# mm_robot_pcb_v6.net
KiCad netlist of a schematic drawn in EAGLE
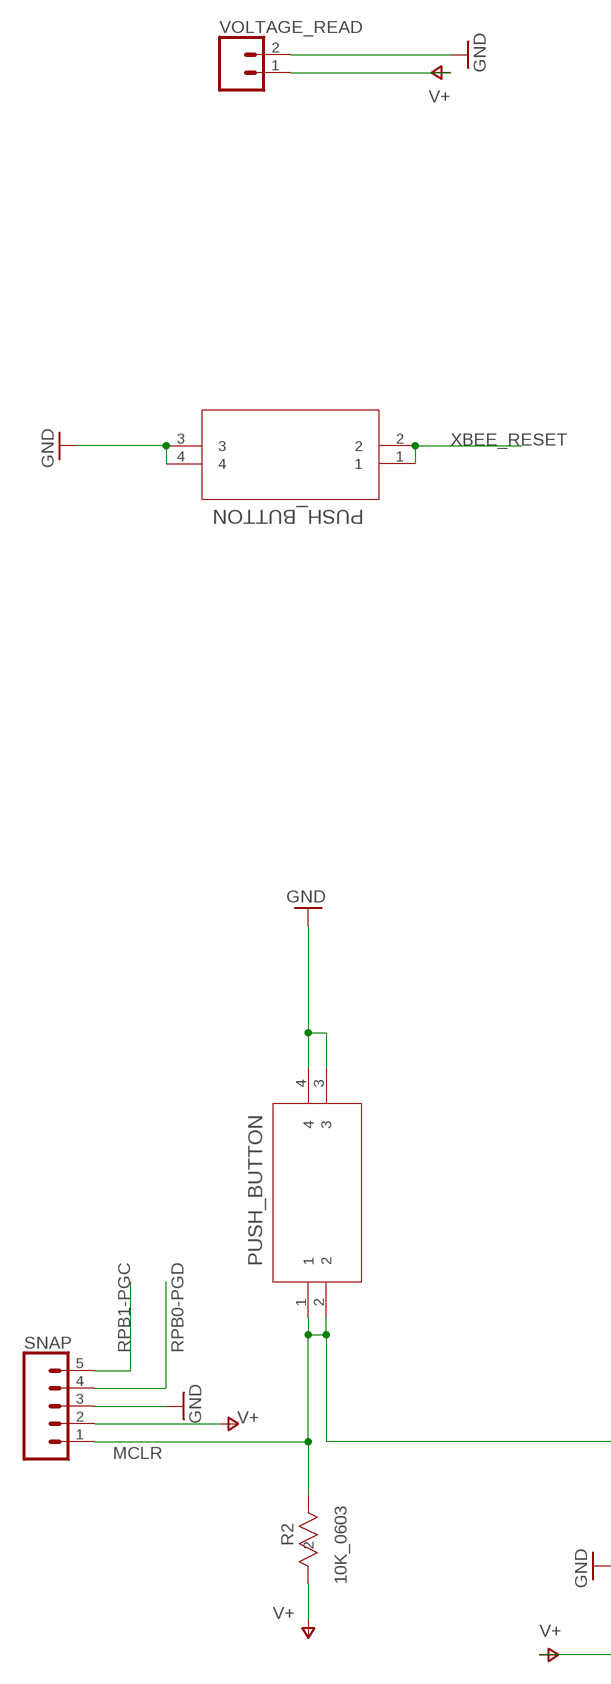
[diagram p0: schematic, sheet 1, part 1 of 2]
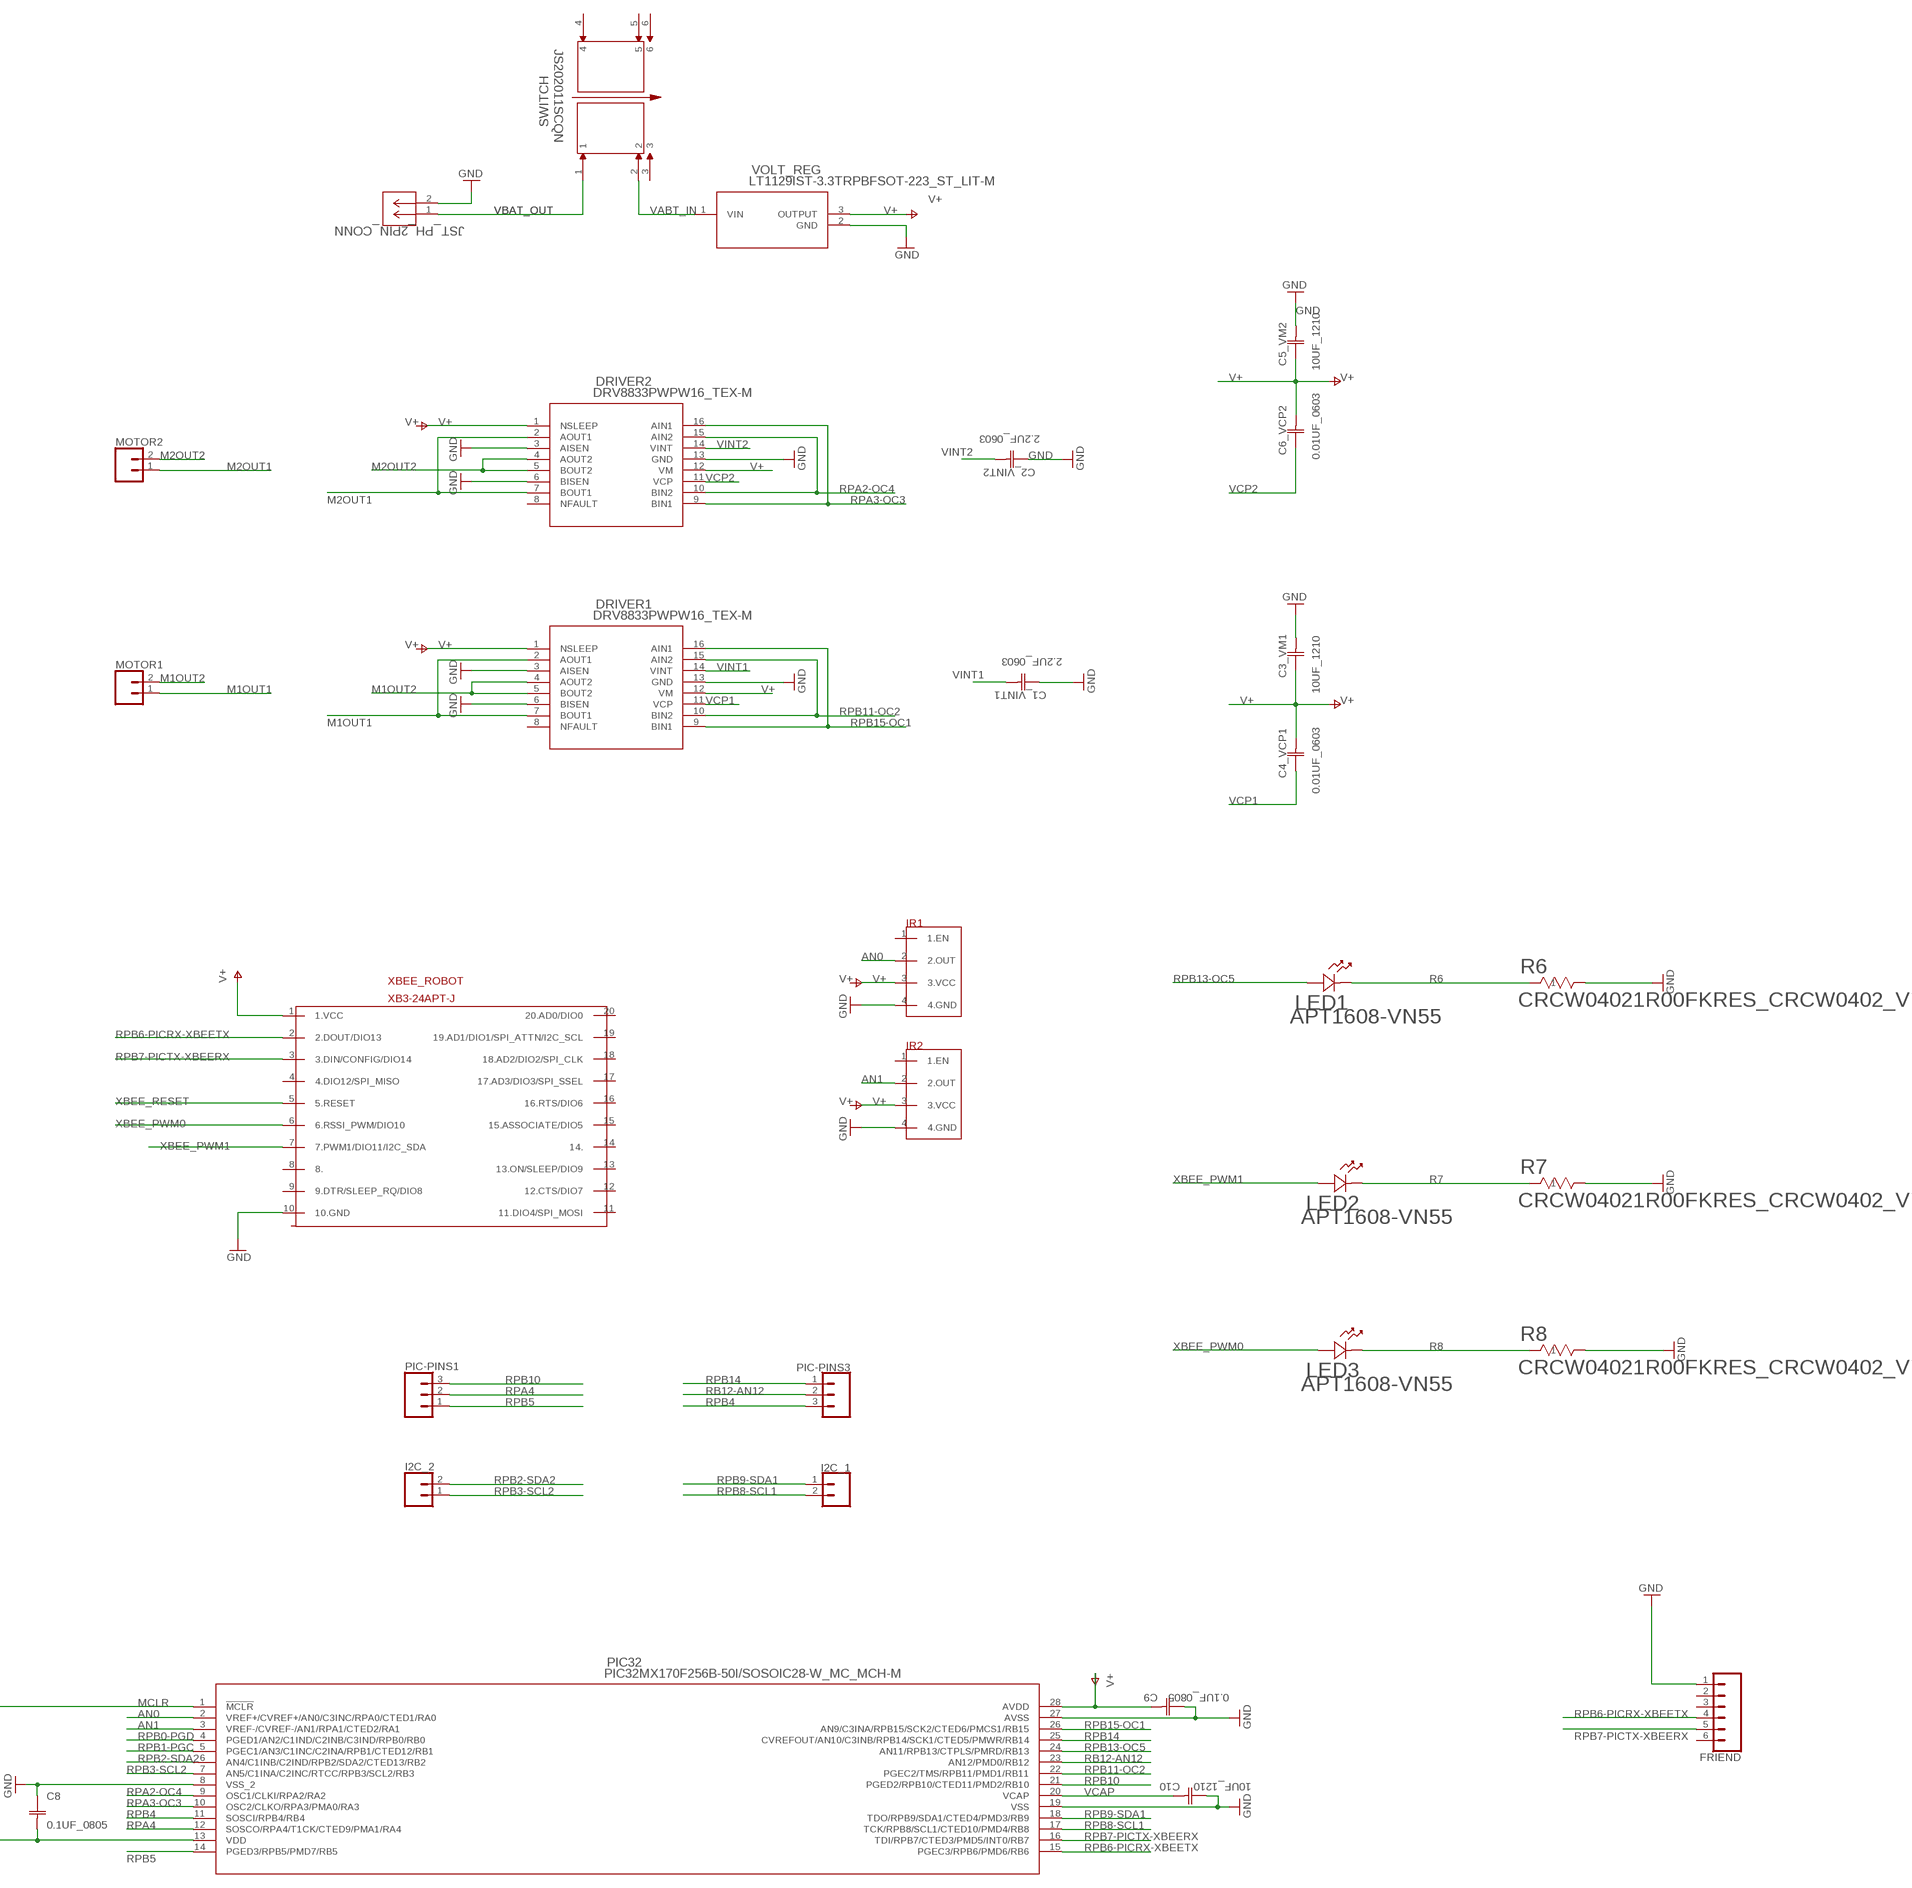
[diagram p1: schematic, sheet 1, part 2 of 2]

(export (version "E")
  (design (tool "Eeschema 10.0.6"))
  (components
    (comp (ref "C1_VINT1")
      (value "2.2UF_0603")
      (footprint "eagle-import:CAP_CL10_SAM-M")
      (fields
        (field (name "MANUFACTURER_PART_NUMBER") "CL10A225KP8NNNC")
        (field (name "COPYRIGHT") "Copyright (C) 2021 Ultra Librarian. All rights reserved.")
      )
      (libsource (lib "eagle-import") (part "CL10A225KP8NNNCCAP_CL10_SAM-M"))
    )
    (comp (ref "C2_VINT2")
      (value "2.2UF_0603")
      (footprint "eagle-import:CAP_CL10_SAM-M")
      (fields
        (field (name "MANUFACTURER_PART_NUMBER") "CL10A225KP8NNNC")
        (field (name "COPYRIGHT") "Copyright (C) 2021 Ultra Librarian. All rights reserved.")
      )
      (libsource (lib "eagle-import") (part "CL10A225KP8NNNCCAP_CL10_SAM-M"))
    )
    (comp (ref "C3_VM1")
      (value "10UF_1210")
      (footprint "eagle-import:CAP_TPS_B_AVX-M")
      (fields
        (field (name "MANUFACTURER_PART_NUMBER") "TPSB106K016R0500")
        (field (name "COPYRIGHT") "Copyright (C) 2021 Ultra Librarian. All rights reserved.")
      )
      (libsource (lib "eagle-import") (part "TPSB106K016R0500CAP_TPS_B_AVX-M"))
    )
    (comp (ref "C4_VCP1")
      (value "0.01UF_0603")
      (footprint "eagle-import:CAP_01UF_0603_X7R_G_AVX")
      (libsource (lib "eagle-import") (part "01UF_CAP"))
    )
    (comp (ref "C5_VM2")
      (value "10UF_1210")
      (footprint "eagle-import:CAP_TPS_B_AVX-M")
      (fields
        (field (name "MANUFACTURER_PART_NUMBER") "TPSB106K016R0500")
        (field (name "COPYRIGHT") "Copyright (C) 2021 Ultra Librarian. All rights reserved.")
      )
      (libsource (lib "eagle-import") (part "TPSB106K016R0500CAP_TPS_B_AVX-M"))
    )
    (comp (ref "C6_VCP2")
      (value "0.01UF_0603")
      (footprint "eagle-import:CAP_01UF_0603_X7R_G_AVX")
      (libsource (lib "eagle-import") (part "01UF_CAP"))
    )
    (comp (ref "C8")
      (value "0.1UF_0805")
      (footprint "eagle-import:CAP_C2012X7R2A104K125AA_TDK-M")
      (fields
        (field (name "MANUFACTURER_PART_NUMBER") "C2012X7R2A104K125AA")
        (field (name "COPYRIGHT") "Copyright (C) 2021 Ultra Librarian. All rights reserved.")
      )
      (libsource (lib "eagle-import") (part "C2012X7R2A104K125AACAP_C2012X7R2A104K125AA_TDK-M"))
    )
    (comp (ref "C9")
      (value "0.1UF_0805")
      (footprint "eagle-import:CAP_C2012X7R2A104K125AA_TDK-M")
      (fields
        (field (name "MANUFACTURER_PART_NUMBER") "C2012X7R2A104K125AA")
        (field (name "COPYRIGHT") "Copyright (C) 2021 Ultra Librarian. All rights reserved.")
      )
      (libsource (lib "eagle-import") (part "C2012X7R2A104K125AACAP_C2012X7R2A104K125AA_TDK-M"))
    )
    (comp (ref "C10")
      (value "10UF_1210")
      (footprint "eagle-import:CAP_TPS_B_AVX-M")
      (fields
        (field (name "MANUFACTURER_PART_NUMBER") "TPSB106K016R0500")
        (field (name "COPYRIGHT") "Copyright (C) 2021 Ultra Librarian. All rights reserved.")
      )
      (libsource (lib "eagle-import") (part "TPSB106K016R0500CAP_TPS_B_AVX-M"))
    )
    (comp (ref "DRIVER1")
      (value "DRV8833PWPW16_TEX-M")
      (footprint "eagle-import:PW16_TEX-M")
      (fields
        (field (name "MANUFACTURER_PART_NUMBER") "DRV8833PW")
        (field (name "COPYRIGHT") "Copyright (C) 2021 Ultra Librarian. All rights reserved.")
      )
      (libsource (lib "eagle-import") (part "DRV8833PWPW16_TEX-M"))
    )
    (comp (ref "DRIVER2")
      (value "DRV8833PWPW16_TEX-M")
      (footprint "eagle-import:PW16_TEX-M")
      (fields
        (field (name "MANUFACTURER_PART_NUMBER") "DRV8833PW")
        (field (name "COPYRIGHT") "Copyright (C) 2021 Ultra Librarian. All rights reserved.")
      )
      (libsource (lib "eagle-import") (part "DRV8833PWPW16_TEX-M"))
    )
    (comp (ref "FRIEND")
      (value "CONN_06NO_SILK_FEMALE_PTH")
      (footprint "eagle-import:1X06_NO_SILK")
      (libsource (lib "eagle-import") (part "CONN_06NO_SILK_FEMALE_PTH"))
    )
    (comp (ref "I2C_1")
      (value "CONN_02")
      (footprint "eagle-import:1X02")
      (libsource (lib "eagle-import") (part "CONN_02"))
    )
    (comp (ref "I2C_2")
      (value "CONN_02")
      (footprint "eagle-import:1X02")
      (libsource (lib "eagle-import") (part "CONN_02"))
    )
    (comp (ref "IR1")
      (value "GP2Y0A60SZLF")
      (footprint "eagle-import:1X04")
      (libsource (lib "eagle-import") (part "GP2Y0A60SZLF"))
    )
    (comp (ref "IR2")
      (value "GP2Y0A60SZLF")
      (footprint "eagle-import:1X04")
      (libsource (lib "eagle-import") (part "GP2Y0A60SZLF"))
    )
    (comp (ref "JST_PH_2PIN_CONN")
      (value "1769")
      (footprint "eagle-import:CONN_1769_ADA")
      (fields (field (name "COPYRIGHT") "Copyright (C) 2021 Ultra Librarian. All rights reserved."))
      (libsource (lib "eagle-import") (part "1769"))
    )
    (comp (ref "LED1")
      (value "APT1608-VN55")
      (footprint "eagle-import:LED_APT1608_KNB")
      (fields (field (name "COPYRIGHT") "Copyright (C) 2021 Ultra Librarian. All rights reserved."))
      (libsource (lib "eagle-import") (part "APT1608-VN55"))
    )
    (comp (ref "LED2")
      (value "APT1608-VN55")
      (footprint "eagle-import:LED_APT1608_KNB")
      (fields (field (name "COPYRIGHT") "Copyright (C) 2021 Ultra Librarian. All rights reserved."))
      (libsource (lib "eagle-import") (part "APT1608-VN55"))
    )
    (comp (ref "LED3")
      (value "APT1608-VN55")
      (footprint "eagle-import:LED_APT1608_KNB")
      (fields (field (name "COPYRIGHT") "Copyright (C) 2021 Ultra Librarian. All rights reserved."))
      (libsource (lib "eagle-import") (part "APT1608-VN55"))
    )
    (comp (ref "MOTOR1")
      (value "CONN_02")
      (footprint "eagle-import:1X02")
      (libsource (lib "eagle-import") (part "CONN_02"))
    )
    (comp (ref "MOTOR2")
      (value "CONN_02")
      (footprint "eagle-import:1X02")
      (libsource (lib "eagle-import") (part "CONN_02"))
    )
    (comp (ref "PIC-PINS1")
      (value "455-1750-1-ND")
      (footprint "eagle-import:1X03")
      (libsource (lib "eagle-import") (part "CONN_03"))
    )
    (comp (ref "PIC-PINS3")
      (value "455-1750-1-ND")
      (footprint "eagle-import:1X03")
      (libsource (lib "eagle-import") (part "CONN_03"))
    )
    (comp (ref "PIC32")
      (value "PIC32MX170F256B-50I/SOSOIC28-W_MC_MCH-M")
      (footprint "eagle-import:SOIC28-W_MC_MCH-M")
      (fields
        (field (name "MANUFACTURER_PART_NUMBER") "PIC32MX170F256B-50I/SO")
        (field (name "COPYRIGHT") "Copyright (C) 2021 Ultra Librarian. All rights reserved.")
      )
      (libsource (lib "eagle-import") (part "PIC32MX170F256B-50I/SOSOIC28-W_MC_MCH-M"))
    )
    (comp (ref "PIC_PB")
      (value "PUSH_BUTTON")
      (footprint "eagle-import:SMT_FS-M")
      (fields
        (field (name "MANUFACTURER_PART_NUMBER") "PTS526 SK15 SMTR2 LFS")
        (field (name "COPYRIGHT") "Copyright (C) 2021 Ultra Librarian. All rights reserved.")
      )
      (libsource (lib "eagle-import") (part "PTS526_SK15_SMTR2_LFSSMT_FS-M"))
    )
    (comp (ref "R2")
      (value "10K_0603")
      (footprint "eagle-import:RES0603_CRG_TYCO_TYC-M")
      (fields
        (field (name "MANUFACTURER_PART_NUMBER") "CRG0603F10K")
        (field (name "COPYRIGHT") "Copyright (C) 2021 Ultra Librarian. All rights reserved.")
      )
      (libsource (lib "eagle-import") (part "CRG0603F10KRES0603_CRG_TYCO_TYC-M"))
    )
    (comp (ref "R6")
      (value "CRCW04021R00FKRES_CRCW0402_VIS-M")
      (footprint "eagle-import:RES_CRCW0402_VIS-M")
      (fields
        (field (name "MANUFACTURER_PART_NUMBER") "CRCW04021R00FK")
        (field (name "COPYRIGHT") "Copyright (C) 2021 Ultra Librarian. All rights reserved.")
      )
      (libsource (lib "eagle-import") (part "CRCW04021R00FKRES_CRCW0402_VIS-M"))
    )
    (comp (ref "R7")
      (value "CRCW04021R00FKRES_CRCW0402_VIS-M")
      (footprint "eagle-import:RES_CRCW0402_VIS-M")
      (fields
        (field (name "MANUFACTURER_PART_NUMBER") "CRCW04021R00FK")
        (field (name "COPYRIGHT") "Copyright (C) 2021 Ultra Librarian. All rights reserved.")
      )
      (libsource (lib "eagle-import") (part "CRCW04021R00FKRES_CRCW0402_VIS-M"))
    )
    (comp (ref "R8")
      (value "CRCW04021R00FKRES_CRCW0402_VIS-M")
      (footprint "eagle-import:RES_CRCW0402_VIS-M")
      (fields
        (field (name "MANUFACTURER_PART_NUMBER") "CRCW04021R00FK")
        (field (name "COPYRIGHT") "Copyright (C) 2021 Ultra Librarian. All rights reserved.")
      )
      (libsource (lib "eagle-import") (part "CRCW04021R00FKRES_CRCW0402_VIS-M"))
    )
    (comp (ref "SNAP")
      (value "CONN_05")
      (footprint "eagle-import:1X05")
      (libsource (lib "eagle-import") (part "CONN_05"))
    )
    (comp (ref "SWITCH")
      (value "JS202011SCQN")
      (footprint "eagle-import:SW_JS202011SCQN")
      (fields (field (name "COPYRIGHT") "Copyright (C) 2021 Ultra Librarian. All rights reserved."))
      (libsource (lib "eagle-import") (part "JS202011SCQN"))
    )
    (comp (ref "VOLTAGE_READ")
      (value "CONN_02")
      (footprint "eagle-import:1X02")
      (libsource (lib "eagle-import") (part "CONN_02"))
    )
    (comp (ref "VOLT_REG")
      (value "LT1129IST-3.3TRPBFSOT-223_ST_LIT-M")
      (footprint "eagle-import:SOT-223_ST_LIT-M")
      (fields
        (field (name "MANUFACTURER_PART_NUMBER") "LT1129IST-3.3#TRPBF")
        (field (name "COPYRIGHT") "Copyright (C) 2021 Ultra Librarian. All rights reserved.")
      )
      (libsource (lib "eagle-import") (part "LT1129IST-3.3TRPBFSOT-223_ST_LIT-M"))
    )
    (comp (ref "XBEE_PB")
      (value "PUSH_BUTTON")
      (footprint "eagle-import:SMT_FS-M")
      (fields
        (field (name "MANUFACTURER_PART_NUMBER") "PTS526 SK15 SMTR2 LFS")
        (field (name "COPYRIGHT") "Copyright (C) 2021 Ultra Librarian. All rights reserved.")
      )
      (libsource (lib "eagle-import") (part "PTS526_SK15_SMTR2_LFSSMT_FS-M"))
    )
    (comp (ref "XBEE_ROBOT")
      (value "XB3-24APT-J")
      (footprint "eagle-import:XB3-24APT-J")
      (libsource (lib "eagle-import") (part "XB3-24APT-J"))
    )
  )
  (nets
    (net (code "1") (name "/AN0") (class "Default")
      (node (ref "IR1") (pin "2") (pinfunction "2.OUT_2") (pintype "bidirectional"))
      (node (ref "PIC32") (pin "2") (pinfunction "VREF+/CVREF+/AN0/C3INC/RPA0/CTED1/RA0_2") (pintype "bidirectional"))
    )
    (net (code "2") (name "/AN1") (class "Default")
      (node (ref "IR2") (pin "2") (pinfunction "2.OUT_2") (pintype "bidirectional"))
      (node (ref "PIC32") (pin "3") (pinfunction "VREF-/CVREF-/AN1/RPA1/CTED2/RA1_3") (pintype "bidirectional"))
    )
    (net (code "3") (name "/M1OUT1") (class "Default")
      (node (ref "DRIVER1") (pin "2") (pinfunction "AOUT1_2") (pintype "output"))
      (node (ref "DRIVER1") (pin "7") (pinfunction "BOUT1_7") (pintype "output"))
      (node (ref "MOTOR1") (pin "1") (pinfunction "1_1") (pintype "passive"))
    )
    (net (code "4") (name "/M1OUT2") (class "Default")
      (node (ref "DRIVER1") (pin "4") (pinfunction "AOUT2_4") (pintype "output"))
      (node (ref "DRIVER1") (pin "5") (pinfunction "BOUT2_5") (pintype "output"))
      (node (ref "MOTOR1") (pin "2") (pinfunction "2_2") (pintype "passive"))
    )
    (net (code "5") (name "/M2OUT1") (class "Default")
      (node (ref "DRIVER2") (pin "2") (pinfunction "AOUT1_2") (pintype "output"))
      (node (ref "DRIVER2") (pin "7") (pinfunction "BOUT1_7") (pintype "output"))
      (node (ref "MOTOR2") (pin "1") (pinfunction "1_1") (pintype "passive"))
    )
    (net (code "6") (name "/M2OUT2") (class "Default")
      (node (ref "DRIVER2") (pin "4") (pinfunction "AOUT2_4") (pintype "output"))
      (node (ref "DRIVER2") (pin "5") (pinfunction "BOUT2_5") (pintype "output"))
      (node (ref "MOTOR2") (pin "2") (pinfunction "2_2") (pintype "passive"))
    )
    (net (code "7") (name "/MCLR") (class "Default")
      (node (ref "PIC32") (pin "1") (pinfunction "~{MCLR}_1") (pintype "bidirectional"))
      (node (ref "PIC_PB") (pin "1") (pinfunction "1_1") (pintype "passive"))
      (node (ref "PIC_PB") (pin "2") (pinfunction "2_2") (pintype "passive"))
      (node (ref "R2") (pin "1") (pinfunction "1_1") (pintype "passive"))
      (node (ref "SNAP") (pin "1") (pinfunction "1_1") (pintype "passive"))
    )
    (net (code "8") (name "/R6") (class "Default")
      (node (ref "LED1") (pin "1") (pinfunction "1_1") (pintype "passive"))
      (node (ref "R6") (pin "1") (pinfunction "1_1") (pintype "passive"))
    )
    (net (code "9") (name "/R7") (class "Default")
      (node (ref "LED2") (pin "1") (pinfunction "1_1") (pintype "passive"))
      (node (ref "R7") (pin "1") (pinfunction "1_1") (pintype "passive"))
    )
    (net (code "10") (name "/R8") (class "Default")
      (node (ref "LED3") (pin "1") (pinfunction "1_1") (pintype "passive"))
      (node (ref "R8") (pin "1") (pinfunction "1_1") (pintype "passive"))
    )
    (net (code "11") (name "/RB12-AN12") (class "Default")
      (node (ref "PIC-PINS3") (pin "2") (pinfunction "2_2") (pintype "passive"))
      (node (ref "PIC32") (pin "23") (pinfunction "AN12/PMD0/RB12_23") (pintype "bidirectional"))
    )
    (net (code "12") (name "/RPA2-OC4") (class "Default")
      (node (ref "DRIVER2") (pin "10") (pinfunction "BIN2_10") (pintype "input"))
      (node (ref "DRIVER2") (pin "15") (pinfunction "AIN2_15") (pintype "input"))
      (node (ref "PIC32") (pin "9") (pinfunction "OSC1/CLKI/RPA2/RA2_9") (pintype "bidirectional"))
    )
    (net (code "13") (name "/RPA3-OC3") (class "Default")
      (node (ref "DRIVER2") (pin "16") (pinfunction "AIN1_16") (pintype "input"))
      (node (ref "DRIVER2") (pin "9") (pinfunction "BIN1_9") (pintype "input"))
      (node (ref "PIC32") (pin "10") (pinfunction "OSC2/CLKO/RPA3/PMA0/RA3_10") (pintype "bidirectional"))
    )
    (net (code "14") (name "/RPA4") (class "Default")
      (node (ref "PIC-PINS1") (pin "2") (pinfunction "2_2") (pintype "passive"))
      (node (ref "PIC32") (pin "12") (pinfunction "SOSCO/RPA4/T1CK/CTED9/PMA1/RA4_12") (pintype "bidirectional"))
    )
    (net (code "15") (name "/RPB0-PGD") (class "Default")
      (node (ref "PIC32") (pin "4") (pinfunction "PGED1/AN2/C1IND/C2INB/C3IND/RPB0/RB0_4") (pintype "bidirectional"))
      (node (ref "SNAP") (pin "4") (pinfunction "4_4") (pintype "passive"))
    )
    (net (code "16") (name "/RPB1-PGC") (class "Default")
      (node (ref "PIC32") (pin "5") (pinfunction "PGEC1/AN3/C1INC/C2INA/RPB1/CTED12/RB1_5") (pintype "bidirectional"))
      (node (ref "SNAP") (pin "5") (pinfunction "5_5") (pintype "passive"))
    )
    (net (code "17") (name "/RPB2-SDA2") (class "Default")
      (node (ref "I2C_2") (pin "2") (pinfunction "2_2") (pintype "passive"))
      (node (ref "PIC32") (pin "6") (pinfunction "AN4/C1INB/C2IND/RPB2/SDA2/CTED13/RB2_6") (pintype "bidirectional"))
    )
    (net (code "18") (name "/RPB3-SCL2") (class "Default")
      (node (ref "I2C_2") (pin "1") (pinfunction "1_1") (pintype "passive"))
      (node (ref "PIC32") (pin "7") (pinfunction "AN5/C1INA/C2INC/RTCC/RPB3/SCL2/RB3_7") (pintype "bidirectional"))
    )
    (net (code "19") (name "/RPB4") (class "Default")
      (node (ref "PIC-PINS3") (pin "3") (pinfunction "3_3") (pintype "passive"))
      (node (ref "PIC32") (pin "11") (pinfunction "SOSCI/RPB4/RB4_11") (pintype "bidirectional"))
    )
    (net (code "20") (name "/RPB5") (class "Default")
      (node (ref "PIC-PINS1") (pin "1") (pinfunction "1_1") (pintype "passive"))
      (node (ref "PIC32") (pin "14") (pinfunction "PGED3/RPB5/PMD7/RB5_14") (pintype "bidirectional"))
    )
    (net (code "21") (name "/RPB6-PICRX-XBEETX") (class "Default")
      (node (ref "FRIEND") (pin "4") (pinfunction "4_4") (pintype "passive"))
      (node (ref "PIC32") (pin "15") (pinfunction "PGEC3/RPB6/PMD6/RB6_15") (pintype "bidirectional"))
      (node (ref "XBEE_ROBOT") (pin "2") (pinfunction "2.DOUT/DIO13_2") (pintype "bidirectional"))
    )
    (net (code "22") (name "/RPB7-PICTX-XBEERX") (class "Default")
      (node (ref "FRIEND") (pin "5") (pinfunction "5_5") (pintype "passive"))
      (node (ref "PIC32") (pin "16") (pinfunction "TDI/RPB7/CTED3/PMD5/INT0/RB7_16") (pintype "bidirectional"))
      (node (ref "XBEE_ROBOT") (pin "3") (pinfunction "3.DIN/CONFIG/DIO14_3") (pintype "bidirectional"))
    )
    (net (code "23") (name "/RPB8-SCL1") (class "Default")
      (node (ref "I2C_1") (pin "2") (pinfunction "2_2") (pintype "passive"))
      (node (ref "PIC32") (pin "17") (pinfunction "TCK/RPB8/SCL1/CTED10/PMD4/RB8_17") (pintype "bidirectional"))
    )
    (net (code "24") (name "/RPB9-SDA1") (class "Default")
      (node (ref "I2C_1") (pin "1") (pinfunction "1_1") (pintype "passive"))
      (node (ref "PIC32") (pin "18") (pinfunction "TDO/RPB9/SDA1/CTED4/PMD3/RB9_18") (pintype "bidirectional"))
    )
    (net (code "25") (name "/RPB10") (class "Default")
      (node (ref "PIC-PINS1") (pin "3") (pinfunction "3_3") (pintype "passive"))
      (node (ref "PIC32") (pin "21") (pinfunction "PGED2/RPB10/CTED11/PMD2/RB10_21") (pintype "bidirectional"))
    )
    (net (code "26") (name "/RPB11-OC2") (class "Default")
      (node (ref "DRIVER1") (pin "10") (pinfunction "BIN2_10") (pintype "input"))
      (node (ref "DRIVER1") (pin "15") (pinfunction "AIN2_15") (pintype "input"))
      (node (ref "PIC32") (pin "22") (pinfunction "PGEC2/TMS/RPB11/PMD1/RB11_22") (pintype "bidirectional"))
    )
    (net (code "27") (name "/RPB13-OC5") (class "Default")
      (node (ref "LED1") (pin "2") (pinfunction "2_2") (pintype "passive"))
      (node (ref "PIC32") (pin "24") (pinfunction "AN11/RPB13/CTPLS/PMRD/RB13_24") (pintype "bidirectional"))
    )
    (net (code "28") (name "/RPB14") (class "Default")
      (node (ref "PIC-PINS3") (pin "1") (pinfunction "1_1") (pintype "passive"))
      (node (ref "PIC32") (pin "25") (pinfunction "CVREFOUT/AN10/C3INB/RPB14/SCK1/CTED5/PMWR/RB14_25") (pintype "bidirectional"))
    )
    (net (code "29") (name "/RPB15-OC1") (class "Default")
      (node (ref "DRIVER1") (pin "16") (pinfunction "AIN1_16") (pintype "input"))
      (node (ref "DRIVER1") (pin "9") (pinfunction "BIN1_9") (pintype "input"))
      (node (ref "PIC32") (pin "26") (pinfunction "AN9/C3INA/RPB15/SCK2/CTED6/PMCS1/RB15_26") (pintype "bidirectional"))
    )
    (net (code "30") (name "/VABT_IN") (class "Default")
      (node (ref "SWITCH") (pin "2") (pinfunction "2_2") (pintype "passive"))
      (node (ref "VOLT_REG") (pin "1") (pinfunction "VIN_1") (pintype "input"))
    )
    (net (code "31") (name "/VBAT_OUT") (class "Default")
      (node (ref "JST_PH_2PIN_CONN") (pin "1") (pinfunction "1_1") (pintype "passive"))
      (node (ref "SWITCH") (pin "1") (pinfunction "1_1") (pintype "passive"))
    )
    (net (code "32") (name "/VCAP") (class "Default")
      (node (ref "C10") (pin "2") (pinfunction "12_2") (pintype "passive"))
      (node (ref "PIC32") (pin "20") (pinfunction "VCAP_20") (pintype "power_in"))
    )
    (net (code "33") (name "/VCP1") (class "Default")
      (node (ref "C4_VCP1") (pin "1") (pinfunction "1_1") (pintype "passive"))
      (node (ref "DRIVER1") (pin "11") (pinfunction "VCP_11") (pintype "bidirectional"))
    )
    (net (code "34") (name "/VCP2") (class "Default")
      (node (ref "C6_VCP2") (pin "1") (pinfunction "1_1") (pintype "passive"))
      (node (ref "DRIVER2") (pin "11") (pinfunction "VCP_11") (pintype "bidirectional"))
    )
    (net (code "35") (name "/VINT1") (class "Default")
      (node (ref "C1_VINT1") (pin "2") (pinfunction "2_2") (pintype "passive"))
      (node (ref "DRIVER1") (pin "14") (pinfunction "VINT_14") (pintype "passive"))
    )
    (net (code "36") (name "/VINT2") (class "Default")
      (node (ref "C2_VINT2") (pin "2") (pinfunction "2_2") (pintype "passive"))
      (node (ref "DRIVER2") (pin "14") (pinfunction "VINT_14") (pintype "passive"))
    )
    (net (code "37") (name "/XBEE_PWM0") (class "Default")
      (node (ref "LED3") (pin "2") (pinfunction "2_2") (pintype "passive"))
      (node (ref "XBEE_ROBOT") (pin "6") (pinfunction "6.RSSI_PWM/DIO10_6") (pintype "bidirectional"))
    )
    (net (code "38") (name "/XBEE_PWM1") (class "Default")
      (node (ref "LED2") (pin "2") (pinfunction "2_2") (pintype "passive"))
      (node (ref "XBEE_ROBOT") (pin "7") (pinfunction "7.PWM1/DIO11/I2C_SDA_7") (pintype "bidirectional"))
    )
    (net (code "39") (name "/XBEE_RESET") (class "Default")
      (node (ref "XBEE_PB") (pin "1") (pinfunction "1_1") (pintype "passive"))
      (node (ref "XBEE_PB") (pin "2") (pinfunction "2_2") (pintype "passive"))
      (node (ref "XBEE_ROBOT") (pin "5") (pinfunction "5.RESET_5") (pintype "bidirectional"))
    )
    (net (code "40") (name "GND") (class "Default")
      (node (ref "C10") (pin "1") (pinfunction "11_1") (pintype "passive"))
      (node (ref "C1_VINT1") (pin "1") (pinfunction "1_1") (pintype "passive"))
      (node (ref "C2_VINT2") (pin "1") (pinfunction "1_1") (pintype "passive"))
      (node (ref "C3_VM1") (pin "2") (pinfunction "12_2") (pintype "passive"))
      (node (ref "C5_VM2") (pin "2") (pinfunction "12_2") (pintype "passive"))
      (node (ref "C8") (pin "1") (pinfunction "1_1") (pintype "passive"))
      (node (ref "C9") (pin "1") (pinfunction "1_1") (pintype "passive"))
      (node (ref "DRIVER1") (pin "13") (pinfunction "GND_13") (pintype "power_in"))
      (node (ref "DRIVER1") (pin "3") (pinfunction "AISEN_3") (pintype "bidirectional"))
      (node (ref "DRIVER1") (pin "6") (pinfunction "BISEN_6") (pintype "bidirectional"))
      (node (ref "DRIVER2") (pin "13") (pinfunction "GND_13") (pintype "power_in"))
      (node (ref "DRIVER2") (pin "3") (pinfunction "AISEN_3") (pintype "bidirectional"))
      (node (ref "DRIVER2") (pin "6") (pinfunction "BISEN_6") (pintype "bidirectional"))
      (node (ref "FRIEND") (pin "1") (pinfunction "1_1") (pintype "passive"))
      (node (ref "IR1") (pin "4") (pinfunction "4.GND_4") (pintype "bidirectional"))
      (node (ref "IR2") (pin "4") (pinfunction "4.GND_4") (pintype "bidirectional"))
      (node (ref "JST_PH_2PIN_CONN") (pin "2") (pinfunction "2_2") (pintype "passive"))
      (node (ref "PIC32") (pin "19") (pinfunction "VSS_19") (pintype "power_in"))
      (node (ref "PIC32") (pin "27") (pinfunction "AVSS_27") (pintype "power_in"))
      (node (ref "PIC32") (pin "8") (pinfunction "VSS_2_8") (pintype "power_in"))
      (node (ref "PIC_PB") (pin "3") (pinfunction "3_3") (pintype "passive"))
      (node (ref "PIC_PB") (pin "4") (pinfunction "4_4") (pintype "passive"))
      (node (ref "R6") (pin "2") (pinfunction "2_2") (pintype "passive"))
      (node (ref "R7") (pin "2") (pinfunction "2_2") (pintype "passive"))
      (node (ref "R8") (pin "2") (pinfunction "2_2") (pintype "passive"))
      (node (ref "SNAP") (pin "3") (pinfunction "3_3") (pintype "passive"))
      (node (ref "VOLTAGE_READ") (pin "2") (pinfunction "2_2") (pintype "passive"))
      (node (ref "VOLT_REG") (pin "2") (pinfunction "GND_2") (pintype "power_in"))
      (node (ref "XBEE_PB") (pin "3") (pinfunction "3_3") (pintype "passive"))
      (node (ref "XBEE_PB") (pin "4") (pinfunction "4_4") (pintype "passive"))
      (node (ref "XBEE_ROBOT") (pin "10") (pinfunction "10.GND_10") (pintype "bidirectional"))
    )
    (net (code "41") (name "V+") (class "Default")
      (node (ref "C3_VM1") (pin "1") (pinfunction "11_1") (pintype "passive"))
      (node (ref "C4_VCP1") (pin "2") (pinfunction "2_2") (pintype "passive"))
      (node (ref "C5_VM2") (pin "1") (pinfunction "11_1") (pintype "passive"))
      (node (ref "C6_VCP2") (pin "2") (pinfunction "2_2") (pintype "passive"))
      (node (ref "C8") (pin "2") (pinfunction "2_2") (pintype "passive"))
      (node (ref "C9") (pin "2") (pinfunction "2_2") (pintype "passive"))
      (node (ref "DRIVER1") (pin "1") (pinfunction "NSLEEP_1") (pintype "input"))
      (node (ref "DRIVER1") (pin "12") (pinfunction "VM_12") (pintype "power_in"))
      (node (ref "DRIVER2") (pin "1") (pinfunction "NSLEEP_1") (pintype "input"))
      (node (ref "DRIVER2") (pin "12") (pinfunction "VM_12") (pintype "power_in"))
      (node (ref "IR1") (pin "3") (pinfunction "3.VCC_3") (pintype "bidirectional"))
      (node (ref "IR2") (pin "3") (pinfunction "3.VCC_3") (pintype "bidirectional"))
      (node (ref "PIC32") (pin "13") (pinfunction "VDD_13") (pintype "power_in"))
      (node (ref "PIC32") (pin "28") (pinfunction "AVDD_28") (pintype "power_in"))
      (node (ref "R2") (pin "2") (pinfunction "2_2") (pintype "passive"))
      (node (ref "SNAP") (pin "2") (pinfunction "2_2") (pintype "passive"))
      (node (ref "VOLTAGE_READ") (pin "1") (pinfunction "1_1") (pintype "passive"))
      (node (ref "VOLT_REG") (pin "3") (pinfunction "OUTPUT_3") (pintype "output"))
      (node (ref "XBEE_ROBOT") (pin "1") (pinfunction "1.VCC_1") (pintype "bidirectional"))
    )
    (net (code "42") (name "unconnected-(DRIVER1-NFAULT-Pad8)") (class "Default")
      (node (ref "DRIVER1") (pin "8") (pinfunction "NFAULT_8") (pintype "output"))
    )
    (net (code "43") (name "unconnected-(DRIVER2-NFAULT-Pad8)") (class "Default")
      (node (ref "DRIVER2") (pin "8") (pinfunction "NFAULT_8") (pintype "output"))
    )
    (net (code "44") (name "unconnected-(FRIEND-Pad2)") (class "Default")
      (node (ref "FRIEND") (pin "2") (pinfunction "2_2") (pintype "passive"))
    )
    (net (code "45") (name "unconnected-(FRIEND-Pad3)") (class "Default")
      (node (ref "FRIEND") (pin "3") (pinfunction "3_3") (pintype "passive"))
    )
    (net (code "46") (name "unconnected-(FRIEND-Pad6)") (class "Default")
      (node (ref "FRIEND") (pin "6") (pinfunction "6_6") (pintype "passive"))
    )
    (net (code "47") (name "unconnected-(IR1-1.EN-Pad1)") (class "Default")
      (node (ref "IR1") (pin "1") (pinfunction "1.EN_1") (pintype "bidirectional"))
    )
    (net (code "48") (name "unconnected-(IR2-1.EN-Pad1)") (class "Default")
      (node (ref "IR2") (pin "1") (pinfunction "1.EN_1") (pintype "bidirectional"))
    )
    (net (code "49") (name "unconnected-(SWITCH-Pad3)") (class "Default")
      (node (ref "SWITCH") (pin "3") (pinfunction "3_3") (pintype "passive"))
    )
    (net (code "50") (name "unconnected-(SWITCH-Pad4)") (class "Default")
      (node (ref "SWITCH") (pin "4") (pinfunction "4_4") (pintype "passive"))
    )
    (net (code "51") (name "unconnected-(SWITCH-Pad5)") (class "Default")
      (node (ref "SWITCH") (pin "5") (pinfunction "5_5") (pintype "passive"))
    )
    (net (code "52") (name "unconnected-(SWITCH-Pad6)") (class "Default")
      (node (ref "SWITCH") (pin "6") (pinfunction "6_6") (pintype "passive"))
    )
    (net (code "53") (name "unconnected-(XBEE_ROBOT-4.DIO12{slash}SPI_MISO-Pad4)") (class "Default")
      (node (ref "XBEE_ROBOT") (pin "4") (pinfunction "4.DIO12/SPI_MISO_4") (pintype "bidirectional"))
    )
    (net (code "54") (name "unconnected-(XBEE_ROBOT-8.-Pad8)") (class "Default")
      (node (ref "XBEE_ROBOT") (pin "8") (pinfunction "8._8") (pintype "bidirectional"))
    )
    (net (code "55") (name "unconnected-(XBEE_ROBOT-9.DTR{slash}SLEEP_RQ{slash}DIO8-Pad9)") (class "Default")
      (node (ref "XBEE_ROBOT") (pin "9") (pinfunction "9.DTR/SLEEP_RQ/DIO8_9") (pintype "bidirectional"))
    )
    (net (code "56") (name "unconnected-(XBEE_ROBOT-11.DIO4{slash}SPI_MOSI-Pad11)") (class "Default")
      (node (ref "XBEE_ROBOT") (pin "11") (pinfunction "11.DIO4/SPI_MOSI_11") (pintype "bidirectional"))
    )
    (net (code "57") (name "unconnected-(XBEE_ROBOT-12.CTS{slash}DIO7-Pad12)") (class "Default")
      (node (ref "XBEE_ROBOT") (pin "12") (pinfunction "12.CTS/DIO7_12") (pintype "bidirectional"))
    )
    (net (code "58") (name "unconnected-(XBEE_ROBOT-13.ON{slash}SLEEP{slash}DIO9-Pad13)") (class "Default")
      (node (ref "XBEE_ROBOT") (pin "13") (pinfunction "13.ON/SLEEP/DIO9_13") (pintype "bidirectional"))
    )
    (net (code "59") (name "unconnected-(XBEE_ROBOT-14.-Pad14)") (class "Default")
      (node (ref "XBEE_ROBOT") (pin "14") (pinfunction "14._14") (pintype "bidirectional"))
    )
    (net (code "60") (name "unconnected-(XBEE_ROBOT-15.ASSOCIATE{slash}DIO5-Pad15)") (class "Default")
      (node (ref "XBEE_ROBOT") (pin "15") (pinfunction "15.ASSOCIATE/DIO5_15") (pintype "bidirectional"))
    )
    (net (code "61") (name "unconnected-(XBEE_ROBOT-16.RTS{slash}DIO6-Pad16)") (class "Default")
      (node (ref "XBEE_ROBOT") (pin "16") (pinfunction "16.RTS/DIO6_16") (pintype "bidirectional"))
    )
    (net (code "62") (name "unconnected-(XBEE_ROBOT-17.AD3{slash}DIO3{slash}SPI_SSEL-Pad17)") (class "Default")
      (node (ref "XBEE_ROBOT") (pin "17") (pinfunction "17.AD3/DIO3/SPI_SSEL_17") (pintype "bidirectional"))
    )
    (net (code "63") (name "unconnected-(XBEE_ROBOT-18.AD2{slash}DIO2{slash}SPI_CLK-Pad18)") (class "Default")
      (node (ref "XBEE_ROBOT") (pin "18") (pinfunction "18.AD2/DIO2/SPI_CLK_18") (pintype "bidirectional"))
    )
    (net (code "64") (name "unconnected-(XBEE_ROBOT-19.AD1{slash}DIO1{slash}SPI_ATTN{slash}I2C_SCL-Pad19)") (class "Default")
      (node (ref "XBEE_ROBOT") (pin "19") (pinfunction "19.AD1/DIO1/SPI_ATTN/I2C_SCL_19") (pintype "bidirectional"))
    )
    (net (code "65") (name "unconnected-(XBEE_ROBOT-20.AD0{slash}DIO0-Pad20)") (class "Default")
      (node (ref "XBEE_ROBOT") (pin "20") (pinfunction "20.AD0/DIO0_20") (pintype "bidirectional"))
    )
  )
)
